# Sensors1-10.net
KiCad netlist of a schematic drawn in Altium Designer
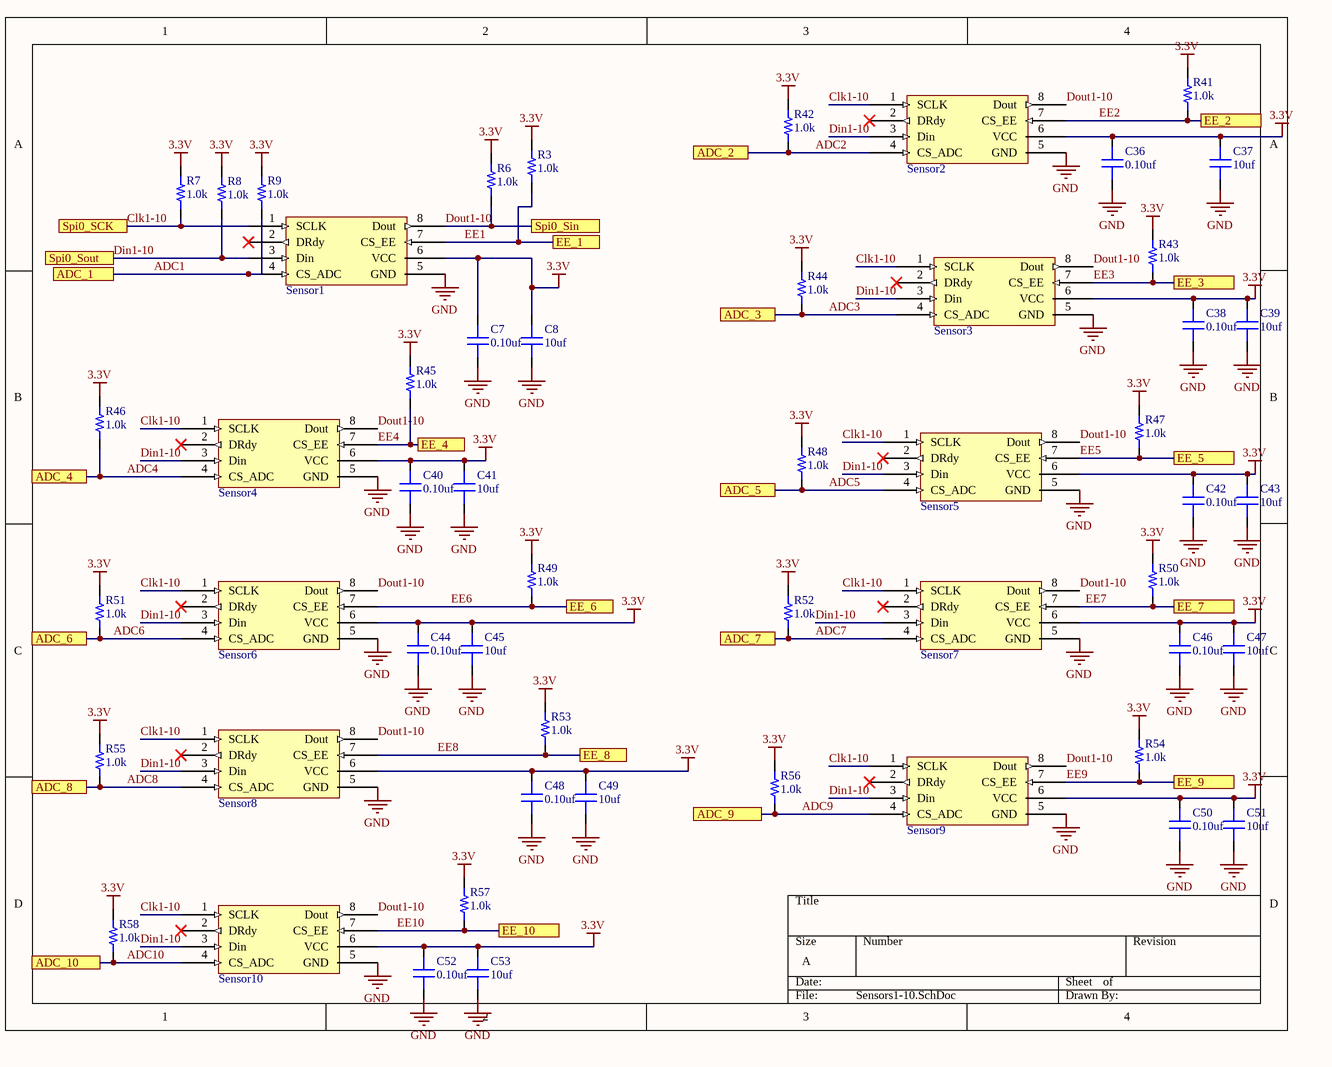
[diagram p0: Sensors1-10.SchDoc]

(export (version "E")
  (design (tool "Eeschema 10.0.6"))
  (components
    (comp (ref "C7")
      (value "0.10uf")
      (footprint "CAP 0603/1608")
      (fields
        (field (name "Comment") "Capacitor MLCC 0.10uf 16V CAP 0603/1608")
        (field (name "CREATED_BY") "Nick Mah")
      )
      (libsource (lib "Altium-Lib") (part "Capacitor"))
    )
    (comp (ref "C8")
      (value "10uf")
      (footprint "CAP 0603/1608")
      (fields
        (field (name "Comment") "Capacitor MLCC 10uf 16V CAP 0603/1608")
        (field (name "CREATED_BY") "Nick Mah")
      )
      (libsource (lib "Altium-Lib") (part "Capacitor"))
    )
    (comp (ref "C36")
      (value "0.10uf")
      (footprint "CAP 0603/1608")
      (fields
        (field (name "Comment") "Capacitor MLCC 0.10uf 16V CAP 0603/1608")
        (field (name "CREATED_BY") "Nick Mah")
      )
      (libsource (lib "Altium-Lib") (part "Capacitor"))
    )
    (comp (ref "C37")
      (value "10uf")
      (footprint "CAP 0603/1608")
      (fields
        (field (name "Comment") "Capacitor MLCC 10uf 16V CAP 0603/1608")
        (field (name "CREATED_BY") "Nick Mah")
      )
      (libsource (lib "Altium-Lib") (part "Capacitor"))
    )
    (comp (ref "C38")
      (value "0.10uf")
      (footprint "CAP 0603/1608")
      (fields
        (field (name "Comment") "Capacitor MLCC 0.10uf 16V CAP 0603/1608")
        (field (name "CREATED_BY") "Nick Mah")
      )
      (libsource (lib "Altium-Lib") (part "Capacitor"))
    )
    (comp (ref "C39")
      (value "10uf")
      (footprint "CAP 0603/1608")
      (fields
        (field (name "Comment") "Capacitor MLCC 10uf 16V CAP 0603/1608")
        (field (name "CREATED_BY") "Nick Mah")
      )
      (libsource (lib "Altium-Lib") (part "Capacitor"))
    )
    (comp (ref "C40")
      (value "0.10uf")
      (footprint "CAP 0603/1608")
      (fields
        (field (name "Comment") "Capacitor MLCC 0.10uf 16V CAP 0603/1608")
        (field (name "CREATED_BY") "Nick Mah")
      )
      (libsource (lib "Altium-Lib") (part "Capacitor"))
    )
    (comp (ref "C41")
      (value "10uf")
      (footprint "CAP 0603/1608")
      (fields
        (field (name "Comment") "Capacitor MLCC 10uf 16V CAP 0603/1608")
        (field (name "CREATED_BY") "Nick Mah")
      )
      (libsource (lib "Altium-Lib") (part "Capacitor"))
    )
    (comp (ref "C42")
      (value "0.10uf")
      (footprint "CAP 0603/1608")
      (fields
        (field (name "Comment") "Capacitor MLCC 0.10uf 16V CAP 0603/1608")
        (field (name "CREATED_BY") "Nick Mah")
      )
      (libsource (lib "Altium-Lib") (part "Capacitor"))
    )
    (comp (ref "C43")
      (value "10uf")
      (footprint "CAP 0603/1608")
      (fields
        (field (name "Comment") "Capacitor MLCC 10uf 16V CAP 0603/1608")
        (field (name "CREATED_BY") "Nick Mah")
      )
      (libsource (lib "Altium-Lib") (part "Capacitor"))
    )
    (comp (ref "C44")
      (value "0.10uf")
      (footprint "CAP 0603/1608")
      (fields
        (field (name "Comment") "Capacitor MLCC 0.10uf 16V CAP 0603/1608")
        (field (name "CREATED_BY") "Nick Mah")
      )
      (libsource (lib "Altium-Lib") (part "Capacitor"))
    )
    (comp (ref "C45")
      (value "10uf")
      (footprint "CAP 0603/1608")
      (fields
        (field (name "Comment") "Capacitor MLCC 10uf 16V CAP 0603/1608")
        (field (name "CREATED_BY") "Nick Mah")
      )
      (libsource (lib "Altium-Lib") (part "Capacitor"))
    )
    (comp (ref "C46")
      (value "0.10uf")
      (footprint "CAP 0603/1608")
      (fields
        (field (name "Comment") "Capacitor MLCC 0.10uf 16V CAP 0603/1608")
        (field (name "CREATED_BY") "Nick Mah")
      )
      (libsource (lib "Altium-Lib") (part "Capacitor"))
    )
    (comp (ref "C47")
      (value "10uf")
      (footprint "CAP 0603/1608")
      (fields
        (field (name "Comment") "Capacitor MLCC 10uf 16V CAP 0603/1608")
        (field (name "CREATED_BY") "Nick Mah")
      )
      (libsource (lib "Altium-Lib") (part "Capacitor"))
    )
    (comp (ref "C48")
      (value "0.10uf")
      (footprint "CAP 0603/1608")
      (fields
        (field (name "Comment") "Capacitor MLCC 0.10uf 16V CAP 0603/1608")
        (field (name "CREATED_BY") "Nick Mah")
      )
      (libsource (lib "Altium-Lib") (part "Capacitor"))
    )
    (comp (ref "C49")
      (value "10uf")
      (footprint "CAP 0603/1608")
      (fields
        (field (name "Comment") "Capacitor MLCC 10uf 16V CAP 0603/1608")
        (field (name "CREATED_BY") "Nick Mah")
      )
      (libsource (lib "Altium-Lib") (part "Capacitor"))
    )
    (comp (ref "C50")
      (value "0.10uf")
      (footprint "CAP 0603/1608")
      (fields
        (field (name "Comment") "Capacitor MLCC 0.10uf 16V CAP 0603/1608")
        (field (name "CREATED_BY") "Nick Mah")
      )
      (libsource (lib "Altium-Lib") (part "Capacitor"))
    )
    (comp (ref "C51")
      (value "10uf")
      (footprint "CAP 0603/1608")
      (fields
        (field (name "Comment") "Capacitor MLCC 10uf 16V CAP 0603/1608")
        (field (name "CREATED_BY") "Nick Mah")
      )
      (libsource (lib "Altium-Lib") (part "Capacitor"))
    )
    (comp (ref "C52")
      (value "0.10uf")
      (footprint "CAP 0603/1608")
      (fields
        (field (name "Comment") "Capacitor MLCC 0.10uf 16V CAP 0603/1608")
        (field (name "CREATED_BY") "Nick Mah")
      )
      (libsource (lib "Altium-Lib") (part "Capacitor"))
    )
    (comp (ref "C53")
      (value "10uf")
      (footprint "CAP 0603/1608")
      (fields
        (field (name "Comment") "Capacitor MLCC 10uf 16V CAP 0603/1608")
        (field (name "CREATED_BY") "Nick Mah")
      )
      (libsource (lib "Altium-Lib") (part "Capacitor"))
    )
    (comp (ref "R3")
      (value "1.0k")
      (footprint "RES 0603/1608")
      (fields
        (field (name "TOLERANCE") "5%")
        (field (name "POWER") "1/10W")
        (field (name "Comment") "Resistor 1.0k 0603 1/10W 5%")
        (field (name "CREATED_BY") "Nick Mah")
      )
      (libsource (lib "Altium-Lib") (part "Resistor"))
    )
    (comp (ref "R6")
      (value "1.0k")
      (footprint "RES 0603/1608")
      (fields
        (field (name "TOLERANCE") "5%")
        (field (name "POWER") "1/10W")
        (field (name "Comment") "Resistor 1.0k 0603 1/10W 5%")
        (field (name "CREATED_BY") "Nick Mah")
      )
      (libsource (lib "Altium-Lib") (part "Resistor"))
    )
    (comp (ref "R7")
      (value "1.0k")
      (footprint "RES 0603/1608")
      (fields
        (field (name "TOLERANCE") "5%")
        (field (name "POWER") "1/10W")
        (field (name "Comment") "Resistor 1.0k 0603 1/10W 5%")
        (field (name "CREATED_BY") "Nick Mah")
      )
      (libsource (lib "Altium-Lib") (part "Resistor"))
    )
    (comp (ref "R8")
      (value "1.0k")
      (footprint "RES 0603/1608")
      (fields
        (field (name "TOLERANCE") "5%")
        (field (name "POWER") "1/10W")
        (field (name "Comment") "Resistor 1.0k 0603 1/10W 5%")
        (field (name "CREATED_BY") "Nick Mah")
      )
      (libsource (lib "Altium-Lib") (part "Resistor"))
    )
    (comp (ref "R9")
      (value "1.0k")
      (footprint "RES 0603/1608")
      (fields
        (field (name "TOLERANCE") "5%")
        (field (name "POWER") "1/10W")
        (field (name "Comment") "Resistor 1.0k 0603 1/10W 5%")
        (field (name "CREATED_BY") "Nick Mah")
      )
      (libsource (lib "Altium-Lib") (part "Resistor"))
    )
    (comp (ref "R41")
      (value "1.0k")
      (footprint "RES 0603/1608")
      (fields
        (field (name "TOLERANCE") "5%")
        (field (name "POWER") "1/10W")
        (field (name "Comment") "Resistor 1.0k 0603 1/10W 5%")
        (field (name "CREATED_BY") "Nick Mah")
      )
      (libsource (lib "Altium-Lib") (part "Resistor"))
    )
    (comp (ref "R42")
      (value "1.0k")
      (footprint "RES 0603/1608")
      (fields
        (field (name "TOLERANCE") "5%")
        (field (name "POWER") "1/10W")
        (field (name "Comment") "Resistor 1.0k 0603 1/10W 5%")
        (field (name "CREATED_BY") "Nick Mah")
      )
      (libsource (lib "Altium-Lib") (part "Resistor"))
    )
    (comp (ref "R43")
      (value "1.0k")
      (footprint "RES 0603/1608")
      (fields
        (field (name "TOLERANCE") "5%")
        (field (name "POWER") "1/10W")
        (field (name "Comment") "Resistor 1.0k 0603 1/10W 5%")
        (field (name "CREATED_BY") "Nick Mah")
      )
      (libsource (lib "Altium-Lib") (part "Resistor"))
    )
    (comp (ref "R44")
      (value "1.0k")
      (footprint "RES 0603/1608")
      (fields
        (field (name "TOLERANCE") "5%")
        (field (name "POWER") "1/10W")
        (field (name "Comment") "Resistor 1.0k 0603 1/10W 5%")
        (field (name "CREATED_BY") "Nick Mah")
      )
      (libsource (lib "Altium-Lib") (part "Resistor"))
    )
    (comp (ref "R45")
      (value "1.0k")
      (footprint "RES 0603/1608")
      (fields
        (field (name "TOLERANCE") "5%")
        (field (name "POWER") "1/10W")
        (field (name "Comment") "Resistor 1.0k 0603 1/10W 5%")
        (field (name "CREATED_BY") "Nick Mah")
      )
      (libsource (lib "Altium-Lib") (part "Resistor"))
    )
    (comp (ref "R46")
      (value "1.0k")
      (footprint "RES 0603/1608")
      (fields
        (field (name "TOLERANCE") "5%")
        (field (name "POWER") "1/10W")
        (field (name "Comment") "Resistor 1.0k 0603 1/10W 5%")
        (field (name "CREATED_BY") "Nick Mah")
      )
      (libsource (lib "Altium-Lib") (part "Resistor"))
    )
    (comp (ref "R47")
      (value "1.0k")
      (footprint "RES 0603/1608")
      (fields
        (field (name "TOLERANCE") "5%")
        (field (name "POWER") "1/10W")
        (field (name "Comment") "Resistor 1.0k 0603 1/10W 5%")
        (field (name "CREATED_BY") "Nick Mah")
      )
      (libsource (lib "Altium-Lib") (part "Resistor"))
    )
    (comp (ref "R48")
      (value "1.0k")
      (footprint "RES 0603/1608")
      (fields
        (field (name "TOLERANCE") "5%")
        (field (name "POWER") "1/10W")
        (field (name "Comment") "Resistor 1.0k 0603 1/10W 5%")
        (field (name "CREATED_BY") "Nick Mah")
      )
      (libsource (lib "Altium-Lib") (part "Resistor"))
    )
    (comp (ref "R49")
      (value "1.0k")
      (footprint "RES 0603/1608")
      (fields
        (field (name "TOLERANCE") "5%")
        (field (name "POWER") "1/10W")
        (field (name "Comment") "Resistor 1.0k 0603 1/10W 5%")
        (field (name "CREATED_BY") "Nick Mah")
      )
      (libsource (lib "Altium-Lib") (part "Resistor"))
    )
    (comp (ref "R50")
      (value "1.0k")
      (footprint "RES 0603/1608")
      (fields
        (field (name "TOLERANCE") "5%")
        (field (name "POWER") "1/10W")
        (field (name "Comment") "Resistor 1.0k 0603 1/10W 5%")
        (field (name "CREATED_BY") "Nick Mah")
      )
      (libsource (lib "Altium-Lib") (part "Resistor"))
    )
    (comp (ref "R51")
      (value "1.0k")
      (footprint "RES 0603/1608")
      (fields
        (field (name "TOLERANCE") "5%")
        (field (name "POWER") "1/10W")
        (field (name "Comment") "Resistor 1.0k 0603 1/10W 5%")
        (field (name "CREATED_BY") "Nick Mah")
      )
      (libsource (lib "Altium-Lib") (part "Resistor"))
    )
    (comp (ref "R52")
      (value "1.0k")
      (footprint "RES 0603/1608")
      (fields
        (field (name "TOLERANCE") "5%")
        (field (name "POWER") "1/10W")
        (field (name "Comment") "Resistor 1.0k 0603 1/10W 5%")
        (field (name "CREATED_BY") "Nick Mah")
      )
      (libsource (lib "Altium-Lib") (part "Resistor"))
    )
    (comp (ref "R53")
      (value "1.0k")
      (footprint "RES 0603/1608")
      (fields
        (field (name "TOLERANCE") "5%")
        (field (name "POWER") "1/10W")
        (field (name "Comment") "Resistor 1.0k 0603 1/10W 5%")
        (field (name "CREATED_BY") "Nick Mah")
      )
      (libsource (lib "Altium-Lib") (part "Resistor"))
    )
    (comp (ref "R54")
      (value "1.0k")
      (footprint "RES 0603/1608")
      (fields
        (field (name "TOLERANCE") "5%")
        (field (name "POWER") "1/10W")
        (field (name "Comment") "Resistor 1.0k 0603 1/10W 5%")
        (field (name "CREATED_BY") "Nick Mah")
      )
      (libsource (lib "Altium-Lib") (part "Resistor"))
    )
    (comp (ref "R55")
      (value "1.0k")
      (footprint "RES 0603/1608")
      (fields
        (field (name "TOLERANCE") "5%")
        (field (name "POWER") "1/10W")
        (field (name "Comment") "Resistor 1.0k 0603 1/10W 5%")
        (field (name "CREATED_BY") "Nick Mah")
      )
      (libsource (lib "Altium-Lib") (part "Resistor"))
    )
    (comp (ref "R56")
      (value "1.0k")
      (footprint "RES 0603/1608")
      (fields
        (field (name "TOLERANCE") "5%")
        (field (name "POWER") "1/10W")
        (field (name "Comment") "Resistor 1.0k 0603 1/10W 5%")
        (field (name "CREATED_BY") "Nick Mah")
      )
      (libsource (lib "Altium-Lib") (part "Resistor"))
    )
    (comp (ref "R57")
      (value "1.0k")
      (footprint "RES 0603/1608")
      (fields
        (field (name "TOLERANCE") "5%")
        (field (name "POWER") "1/10W")
        (field (name "Comment") "Resistor 1.0k 0603 1/10W 5%")
        (field (name "CREATED_BY") "Nick Mah")
      )
      (libsource (lib "Altium-Lib") (part "Resistor"))
    )
    (comp (ref "R58")
      (value "1.0k")
      (footprint "RES 0603/1608")
      (fields
        (field (name "TOLERANCE") "5%")
        (field (name "POWER") "1/10W")
        (field (name "Comment") "Resistor 1.0k 0603 1/10W 5%")
        (field (name "CREATED_BY") "Nick Mah")
      )
      (libsource (lib "Altium-Lib") (part "Resistor"))
    )
    (comp (ref "Sensor1")
      (value "for Aero Pressure Sensor Board")
      (footprint "RSCMJJM005NDSE3 Pressure Sensor")
      (description "RSCMJJM005NDSE3 Pressure Sensor")
      (libsource (lib "Altium-Lib") (part "RSCMJJM005NDSE3 Pressure Sensor"))
    )
    (comp (ref "Sensor2")
      (value "for Aero Pressure Sensor Board")
      (footprint "RSCMJJM005NDSE3 Pressure Sensor")
      (description "RSCMJJM005NDSE3 Pressure Sensor")
      (libsource (lib "Altium-Lib") (part "RSCMJJM005NDSE3 Pressure Sensor"))
    )
    (comp (ref "Sensor3")
      (value "for Aero Pressure Sensor Board")
      (footprint "RSCMJJM005NDSE3 Pressure Sensor")
      (description "RSCMJJM005NDSE3 Pressure Sensor")
      (libsource (lib "Altium-Lib") (part "RSCMJJM005NDSE3 Pressure Sensor"))
    )
    (comp (ref "Sensor4")
      (value "for Aero Pressure Sensor Board")
      (footprint "RSCMJJM005NDSE3 Pressure Sensor")
      (description "RSCMJJM005NDSE3 Pressure Sensor")
      (libsource (lib "Altium-Lib") (part "RSCMJJM005NDSE3 Pressure Sensor"))
    )
    (comp (ref "Sensor5")
      (value "for Aero Pressure Sensor Board")
      (footprint "RSCMJJM005NDSE3 Pressure Sensor")
      (description "RSCMJJM005NDSE3 Pressure Sensor")
      (libsource (lib "Altium-Lib") (part "RSCMJJM005NDSE3 Pressure Sensor"))
    )
    (comp (ref "Sensor6")
      (value "for Aero Pressure Sensor Board")
      (footprint "RSCMJJM005NDSE3 Pressure Sensor")
      (description "RSCMJJM005NDSE3 Pressure Sensor")
      (libsource (lib "Altium-Lib") (part "RSCMJJM005NDSE3 Pressure Sensor"))
    )
    (comp (ref "Sensor7")
      (value "for Aero Pressure Sensor Board")
      (footprint "RSCMJJM005NDSE3 Pressure Sensor")
      (description "RSCMJJM005NDSE3 Pressure Sensor")
      (libsource (lib "Altium-Lib") (part "RSCMJJM005NDSE3 Pressure Sensor"))
    )
    (comp (ref "Sensor8")
      (value "for Aero Pressure Sensor Board")
      (footprint "RSCMJJM005NDSE3 Pressure Sensor")
      (description "RSCMJJM005NDSE3 Pressure Sensor")
      (libsource (lib "Altium-Lib") (part "RSCMJJM005NDSE3 Pressure Sensor"))
    )
    (comp (ref "Sensor9")
      (value "for Aero Pressure Sensor Board")
      (footprint "RSCMJJM005NDSE3 Pressure Sensor")
      (description "RSCMJJM005NDSE3 Pressure Sensor")
      (libsource (lib "Altium-Lib") (part "RSCMJJM005NDSE3 Pressure Sensor"))
    )
    (comp (ref "Sensor10")
      (value "for Aero Pressure Sensor Board")
      (footprint "RSCMJJM005NDSE3 Pressure Sensor")
      (description "RSCMJJM005NDSE3 Pressure Sensor")
      (libsource (lib "Altium-Lib") (part "RSCMJJM005NDSE3 Pressure Sensor"))
    )
  )
  (nets
    (net (code "1") (name "/ADC1") (class "Default")
      (node (ref "R9") (pin "1") (pinfunction "1_1") (pintype "passive"))
      (node (ref "Sensor1") (pin "4") (pinfunction "CS_ADC_4") (pintype "input"))
    )
    (net (code "2") (name "/ADC2") (class "Default")
      (node (ref "R42") (pin "1") (pinfunction "1_1") (pintype "passive"))
      (node (ref "Sensor2") (pin "4") (pinfunction "CS_ADC_4") (pintype "input"))
    )
    (net (code "3") (name "/ADC3") (class "Default")
      (node (ref "R44") (pin "1") (pinfunction "1_1") (pintype "passive"))
      (node (ref "Sensor3") (pin "4") (pinfunction "CS_ADC_4") (pintype "input"))
    )
    (net (code "4") (name "/ADC4") (class "Default")
      (node (ref "R46") (pin "1") (pinfunction "1_1") (pintype "passive"))
      (node (ref "Sensor4") (pin "4") (pinfunction "CS_ADC_4") (pintype "input"))
    )
    (net (code "5") (name "/ADC5") (class "Default")
      (node (ref "R48") (pin "1") (pinfunction "1_1") (pintype "passive"))
      (node (ref "Sensor5") (pin "4") (pinfunction "CS_ADC_4") (pintype "input"))
    )
    (net (code "6") (name "/ADC6") (class "Default")
      (node (ref "R51") (pin "1") (pinfunction "1_1") (pintype "passive"))
      (node (ref "Sensor6") (pin "4") (pinfunction "CS_ADC_4") (pintype "input"))
    )
    (net (code "7") (name "/ADC7") (class "Default")
      (node (ref "R52") (pin "1") (pinfunction "1_1") (pintype "passive"))
      (node (ref "Sensor7") (pin "4") (pinfunction "CS_ADC_4") (pintype "input"))
    )
    (net (code "8") (name "/ADC8") (class "Default")
      (node (ref "R55") (pin "1") (pinfunction "1_1") (pintype "passive"))
      (node (ref "Sensor8") (pin "4") (pinfunction "CS_ADC_4") (pintype "input"))
    )
    (net (code "9") (name "/ADC9") (class "Default")
      (node (ref "R56") (pin "1") (pinfunction "1_1") (pintype "passive"))
      (node (ref "Sensor9") (pin "4") (pinfunction "CS_ADC_4") (pintype "input"))
    )
    (net (code "10") (name "/ADC10") (class "Default")
      (node (ref "R58") (pin "1") (pinfunction "1_1") (pintype "passive"))
      (node (ref "Sensor10") (pin "4") (pinfunction "CS_ADC_4") (pintype "input"))
    )
    (net (code "11") (name "/Clk1-10") (class "Default")
      (node (ref "R7") (pin "1") (pinfunction "1_1") (pintype "passive"))
      (node (ref "Sensor1") (pin "1") (pinfunction "SCLK_1") (pintype "input"))
      (node (ref "Sensor10") (pin "1") (pinfunction "SCLK_1") (pintype "input"))
      (node (ref "Sensor2") (pin "1") (pinfunction "SCLK_1") (pintype "input"))
      (node (ref "Sensor3") (pin "1") (pinfunction "SCLK_1") (pintype "input"))
      (node (ref "Sensor4") (pin "1") (pinfunction "SCLK_1") (pintype "input"))
      (node (ref "Sensor5") (pin "1") (pinfunction "SCLK_1") (pintype "input"))
      (node (ref "Sensor6") (pin "1") (pinfunction "SCLK_1") (pintype "input"))
      (node (ref "Sensor7") (pin "1") (pinfunction "SCLK_1") (pintype "input"))
      (node (ref "Sensor8") (pin "1") (pinfunction "SCLK_1") (pintype "input"))
      (node (ref "Sensor9") (pin "1") (pinfunction "SCLK_1") (pintype "input"))
    )
    (net (code "12") (name "/Din1-10") (class "Default")
      (node (ref "R8") (pin "1") (pinfunction "1_1") (pintype "passive"))
      (node (ref "Sensor1") (pin "3") (pinfunction "Din_3") (pintype "input"))
      (node (ref "Sensor10") (pin "3") (pinfunction "Din_3") (pintype "input"))
      (node (ref "Sensor2") (pin "3") (pinfunction "Din_3") (pintype "input"))
      (node (ref "Sensor3") (pin "3") (pinfunction "Din_3") (pintype "input"))
      (node (ref "Sensor4") (pin "3") (pinfunction "Din_3") (pintype "input"))
      (node (ref "Sensor5") (pin "3") (pinfunction "Din_3") (pintype "input"))
      (node (ref "Sensor6") (pin "3") (pinfunction "Din_3") (pintype "input"))
      (node (ref "Sensor7") (pin "3") (pinfunction "Din_3") (pintype "input"))
      (node (ref "Sensor8") (pin "3") (pinfunction "Din_3") (pintype "input"))
      (node (ref "Sensor9") (pin "3") (pinfunction "Din_3") (pintype "input"))
    )
    (net (code "13") (name "/Dout1-10") (class "Default")
      (node (ref "R6") (pin "1") (pinfunction "1_1") (pintype "passive"))
      (node (ref "Sensor1") (pin "8") (pinfunction "Dout_8") (pintype "output"))
      (node (ref "Sensor10") (pin "8") (pinfunction "Dout_8") (pintype "output"))
      (node (ref "Sensor2") (pin "8") (pinfunction "Dout_8") (pintype "output"))
      (node (ref "Sensor3") (pin "8") (pinfunction "Dout_8") (pintype "output"))
      (node (ref "Sensor4") (pin "8") (pinfunction "Dout_8") (pintype "output"))
      (node (ref "Sensor5") (pin "8") (pinfunction "Dout_8") (pintype "output"))
      (node (ref "Sensor6") (pin "8") (pinfunction "Dout_8") (pintype "output"))
      (node (ref "Sensor7") (pin "8") (pinfunction "Dout_8") (pintype "output"))
      (node (ref "Sensor8") (pin "8") (pinfunction "Dout_8") (pintype "output"))
      (node (ref "Sensor9") (pin "8") (pinfunction "Dout_8") (pintype "output"))
    )
    (net (code "14") (name "/EE1") (class "Default")
      (node (ref "R3") (pin "1") (pinfunction "1_1") (pintype "passive"))
      (node (ref "Sensor1") (pin "7") (pinfunction "CS_EE_7") (pintype "input"))
    )
    (net (code "15") (name "/EE2") (class "Default")
      (node (ref "R41") (pin "1") (pinfunction "1_1") (pintype "passive"))
      (node (ref "Sensor2") (pin "7") (pinfunction "CS_EE_7") (pintype "input"))
    )
    (net (code "16") (name "/EE3") (class "Default")
      (node (ref "R43") (pin "1") (pinfunction "1_1") (pintype "passive"))
      (node (ref "Sensor3") (pin "7") (pinfunction "CS_EE_7") (pintype "input"))
    )
    (net (code "17") (name "/EE4") (class "Default")
      (node (ref "R45") (pin "1") (pinfunction "1_1") (pintype "passive"))
      (node (ref "Sensor4") (pin "7") (pinfunction "CS_EE_7") (pintype "input"))
    )
    (net (code "18") (name "/EE5") (class "Default")
      (node (ref "R47") (pin "1") (pinfunction "1_1") (pintype "passive"))
      (node (ref "Sensor5") (pin "7") (pinfunction "CS_EE_7") (pintype "input"))
    )
    (net (code "19") (name "/EE6") (class "Default")
      (node (ref "R49") (pin "1") (pinfunction "1_1") (pintype "passive"))
      (node (ref "Sensor6") (pin "7") (pinfunction "CS_EE_7") (pintype "input"))
    )
    (net (code "20") (name "/EE7") (class "Default")
      (node (ref "R50") (pin "1") (pinfunction "1_1") (pintype "passive"))
      (node (ref "Sensor7") (pin "7") (pinfunction "CS_EE_7") (pintype "input"))
    )
    (net (code "21") (name "/EE8") (class "Default")
      (node (ref "R53") (pin "1") (pinfunction "1_1") (pintype "passive"))
      (node (ref "Sensor8") (pin "7") (pinfunction "CS_EE_7") (pintype "input"))
    )
    (net (code "22") (name "/EE9") (class "Default")
      (node (ref "R54") (pin "1") (pinfunction "1_1") (pintype "passive"))
      (node (ref "Sensor9") (pin "7") (pinfunction "CS_EE_7") (pintype "input"))
    )
    (net (code "23") (name "/EE10") (class "Default")
      (node (ref "R57") (pin "1") (pinfunction "1_1") (pintype "passive"))
      (node (ref "Sensor10") (pin "7") (pinfunction "CS_EE_7") (pintype "input"))
    )
    (net (code "24") (name "3.3V") (class "Default")
      (node (ref "C36") (pin "2") (pinfunction "2_2") (pintype "passive"))
      (node (ref "C37") (pin "2") (pinfunction "2_2") (pintype "passive"))
      (node (ref "C38") (pin "2") (pinfunction "2_2") (pintype "passive"))
      (node (ref "C39") (pin "2") (pinfunction "2_2") (pintype "passive"))
      (node (ref "C40") (pin "2") (pinfunction "2_2") (pintype "passive"))
      (node (ref "C41") (pin "2") (pinfunction "2_2") (pintype "passive"))
      (node (ref "C42") (pin "2") (pinfunction "2_2") (pintype "passive"))
      (node (ref "C43") (pin "2") (pinfunction "2_2") (pintype "passive"))
      (node (ref "C44") (pin "2") (pinfunction "2_2") (pintype "passive"))
      (node (ref "C45") (pin "2") (pinfunction "2_2") (pintype "passive"))
      (node (ref "C46") (pin "2") (pinfunction "2_2") (pintype "passive"))
      (node (ref "C47") (pin "2") (pinfunction "2_2") (pintype "passive"))
      (node (ref "C48") (pin "2") (pinfunction "2_2") (pintype "passive"))
      (node (ref "C49") (pin "2") (pinfunction "2_2") (pintype "passive"))
      (node (ref "C50") (pin "2") (pinfunction "2_2") (pintype "passive"))
      (node (ref "C51") (pin "2") (pinfunction "2_2") (pintype "passive"))
      (node (ref "C52") (pin "2") (pinfunction "2_2") (pintype "passive"))
      (node (ref "C53") (pin "2") (pinfunction "2_2") (pintype "passive"))
      (node (ref "C7") (pin "2") (pinfunction "2_2") (pintype "passive"))
      (node (ref "C8") (pin "2") (pinfunction "2_2") (pintype "passive"))
      (node (ref "R3") (pin "2") (pinfunction "2_2") (pintype "passive"))
      (node (ref "R41") (pin "2") (pinfunction "2_2") (pintype "passive"))
      (node (ref "R42") (pin "2") (pinfunction "2_2") (pintype "passive"))
      (node (ref "R43") (pin "2") (pinfunction "2_2") (pintype "passive"))
      (node (ref "R44") (pin "2") (pinfunction "2_2") (pintype "passive"))
      (node (ref "R45") (pin "2") (pinfunction "2_2") (pintype "passive"))
      (node (ref "R46") (pin "2") (pinfunction "2_2") (pintype "passive"))
      (node (ref "R47") (pin "2") (pinfunction "2_2") (pintype "passive"))
      (node (ref "R48") (pin "2") (pinfunction "2_2") (pintype "passive"))
      (node (ref "R49") (pin "2") (pinfunction "2_2") (pintype "passive"))
      (node (ref "R50") (pin "2") (pinfunction "2_2") (pintype "passive"))
      (node (ref "R51") (pin "2") (pinfunction "2_2") (pintype "passive"))
      (node (ref "R52") (pin "2") (pinfunction "2_2") (pintype "passive"))
      (node (ref "R53") (pin "2") (pinfunction "2_2") (pintype "passive"))
      (node (ref "R54") (pin "2") (pinfunction "2_2") (pintype "passive"))
      (node (ref "R55") (pin "2") (pinfunction "2_2") (pintype "passive"))
      (node (ref "R56") (pin "2") (pinfunction "2_2") (pintype "passive"))
      (node (ref "R57") (pin "2") (pinfunction "2_2") (pintype "passive"))
      (node (ref "R58") (pin "2") (pinfunction "2_2") (pintype "passive"))
      (node (ref "R6") (pin "2") (pinfunction "2_2") (pintype "passive"))
      (node (ref "R7") (pin "2") (pinfunction "2_2") (pintype "passive"))
      (node (ref "R8") (pin "2") (pinfunction "2_2") (pintype "passive"))
      (node (ref "R9") (pin "2") (pinfunction "2_2") (pintype "passive"))
      (node (ref "Sensor1") (pin "6") (pinfunction "VCC_6") (pintype "power_in"))
      (node (ref "Sensor10") (pin "6") (pinfunction "VCC_6") (pintype "power_in"))
      (node (ref "Sensor2") (pin "6") (pinfunction "VCC_6") (pintype "power_in"))
      (node (ref "Sensor3") (pin "6") (pinfunction "VCC_6") (pintype "power_in"))
      (node (ref "Sensor4") (pin "6") (pinfunction "VCC_6") (pintype "power_in"))
      (node (ref "Sensor5") (pin "6") (pinfunction "VCC_6") (pintype "power_in"))
      (node (ref "Sensor6") (pin "6") (pinfunction "VCC_6") (pintype "power_in"))
      (node (ref "Sensor7") (pin "6") (pinfunction "VCC_6") (pintype "power_in"))
      (node (ref "Sensor8") (pin "6") (pinfunction "VCC_6") (pintype "power_in"))
      (node (ref "Sensor9") (pin "6") (pinfunction "VCC_6") (pintype "power_in"))
    )
    (net (code "25") (name "GND") (class "Default")
      (node (ref "C36") (pin "1") (pinfunction "1_1") (pintype "passive"))
      (node (ref "C37") (pin "1") (pinfunction "1_1") (pintype "passive"))
      (node (ref "C38") (pin "1") (pinfunction "1_1") (pintype "passive"))
      (node (ref "C39") (pin "1") (pinfunction "1_1") (pintype "passive"))
      (node (ref "C40") (pin "1") (pinfunction "1_1") (pintype "passive"))
      (node (ref "C41") (pin "1") (pinfunction "1_1") (pintype "passive"))
      (node (ref "C42") (pin "1") (pinfunction "1_1") (pintype "passive"))
      (node (ref "C43") (pin "1") (pinfunction "1_1") (pintype "passive"))
      (node (ref "C44") (pin "1") (pinfunction "1_1") (pintype "passive"))
      (node (ref "C45") (pin "1") (pinfunction "1_1") (pintype "passive"))
      (node (ref "C46") (pin "1") (pinfunction "1_1") (pintype "passive"))
      (node (ref "C47") (pin "1") (pinfunction "1_1") (pintype "passive"))
      (node (ref "C48") (pin "1") (pinfunction "1_1") (pintype "passive"))
      (node (ref "C49") (pin "1") (pinfunction "1_1") (pintype "passive"))
      (node (ref "C50") (pin "1") (pinfunction "1_1") (pintype "passive"))
      (node (ref "C51") (pin "1") (pinfunction "1_1") (pintype "passive"))
      (node (ref "C52") (pin "1") (pinfunction "1_1") (pintype "passive"))
      (node (ref "C53") (pin "1") (pinfunction "1_1") (pintype "passive"))
      (node (ref "C7") (pin "1") (pinfunction "1_1") (pintype "passive"))
      (node (ref "C8") (pin "1") (pinfunction "1_1") (pintype "passive"))
      (node (ref "Sensor1") (pin "5") (pinfunction "GND_5") (pintype "power_in"))
      (node (ref "Sensor10") (pin "5") (pinfunction "GND_5") (pintype "power_in"))
      (node (ref "Sensor2") (pin "5") (pinfunction "GND_5") (pintype "power_in"))
      (node (ref "Sensor3") (pin "5") (pinfunction "GND_5") (pintype "power_in"))
      (node (ref "Sensor4") (pin "5") (pinfunction "GND_5") (pintype "power_in"))
      (node (ref "Sensor5") (pin "5") (pinfunction "GND_5") (pintype "power_in"))
      (node (ref "Sensor6") (pin "5") (pinfunction "GND_5") (pintype "power_in"))
      (node (ref "Sensor7") (pin "5") (pinfunction "GND_5") (pintype "power_in"))
      (node (ref "Sensor8") (pin "5") (pinfunction "GND_5") (pintype "power_in"))
      (node (ref "Sensor9") (pin "5") (pinfunction "GND_5") (pintype "power_in"))
    )
    (net (code "26") (name "unconnected-(Sensor1-DRdy-Pad2)") (class "Default")
      (node (ref "Sensor1") (pin "2") (pinfunction "DRdy_2") (pintype "output+no_connect"))
    )
    (net (code "27") (name "unconnected-(Sensor2-DRdy-Pad2)") (class "Default")
      (node (ref "Sensor2") (pin "2") (pinfunction "DRdy_2") (pintype "output+no_connect"))
    )
    (net (code "28") (name "unconnected-(Sensor3-DRdy-Pad2)") (class "Default")
      (node (ref "Sensor3") (pin "2") (pinfunction "DRdy_2") (pintype "output+no_connect"))
    )
    (net (code "29") (name "unconnected-(Sensor4-DRdy-Pad2)") (class "Default")
      (node (ref "Sensor4") (pin "2") (pinfunction "DRdy_2") (pintype "output+no_connect"))
    )
    (net (code "30") (name "unconnected-(Sensor5-DRdy-Pad2)") (class "Default")
      (node (ref "Sensor5") (pin "2") (pinfunction "DRdy_2") (pintype "output+no_connect"))
    )
    (net (code "31") (name "unconnected-(Sensor6-DRdy-Pad2)") (class "Default")
      (node (ref "Sensor6") (pin "2") (pinfunction "DRdy_2") (pintype "output+no_connect"))
    )
    (net (code "32") (name "unconnected-(Sensor7-DRdy-Pad2)") (class "Default")
      (node (ref "Sensor7") (pin "2") (pinfunction "DRdy_2") (pintype "output+no_connect"))
    )
    (net (code "33") (name "unconnected-(Sensor8-DRdy-Pad2)") (class "Default")
      (node (ref "Sensor8") (pin "2") (pinfunction "DRdy_2") (pintype "output+no_connect"))
    )
    (net (code "34") (name "unconnected-(Sensor9-DRdy-Pad2)") (class "Default")
      (node (ref "Sensor9") (pin "2") (pinfunction "DRdy_2") (pintype "output+no_connect"))
    )
    (net (code "35") (name "unconnected-(Sensor10-DRdy-Pad2)") (class "Default")
      (node (ref "Sensor10") (pin "2") (pinfunction "DRdy_2") (pintype "output+no_connect"))
    )
  )
)
